# controle_motor_chave.net
KiCad netlist of a schematic drawn in Altium Designer
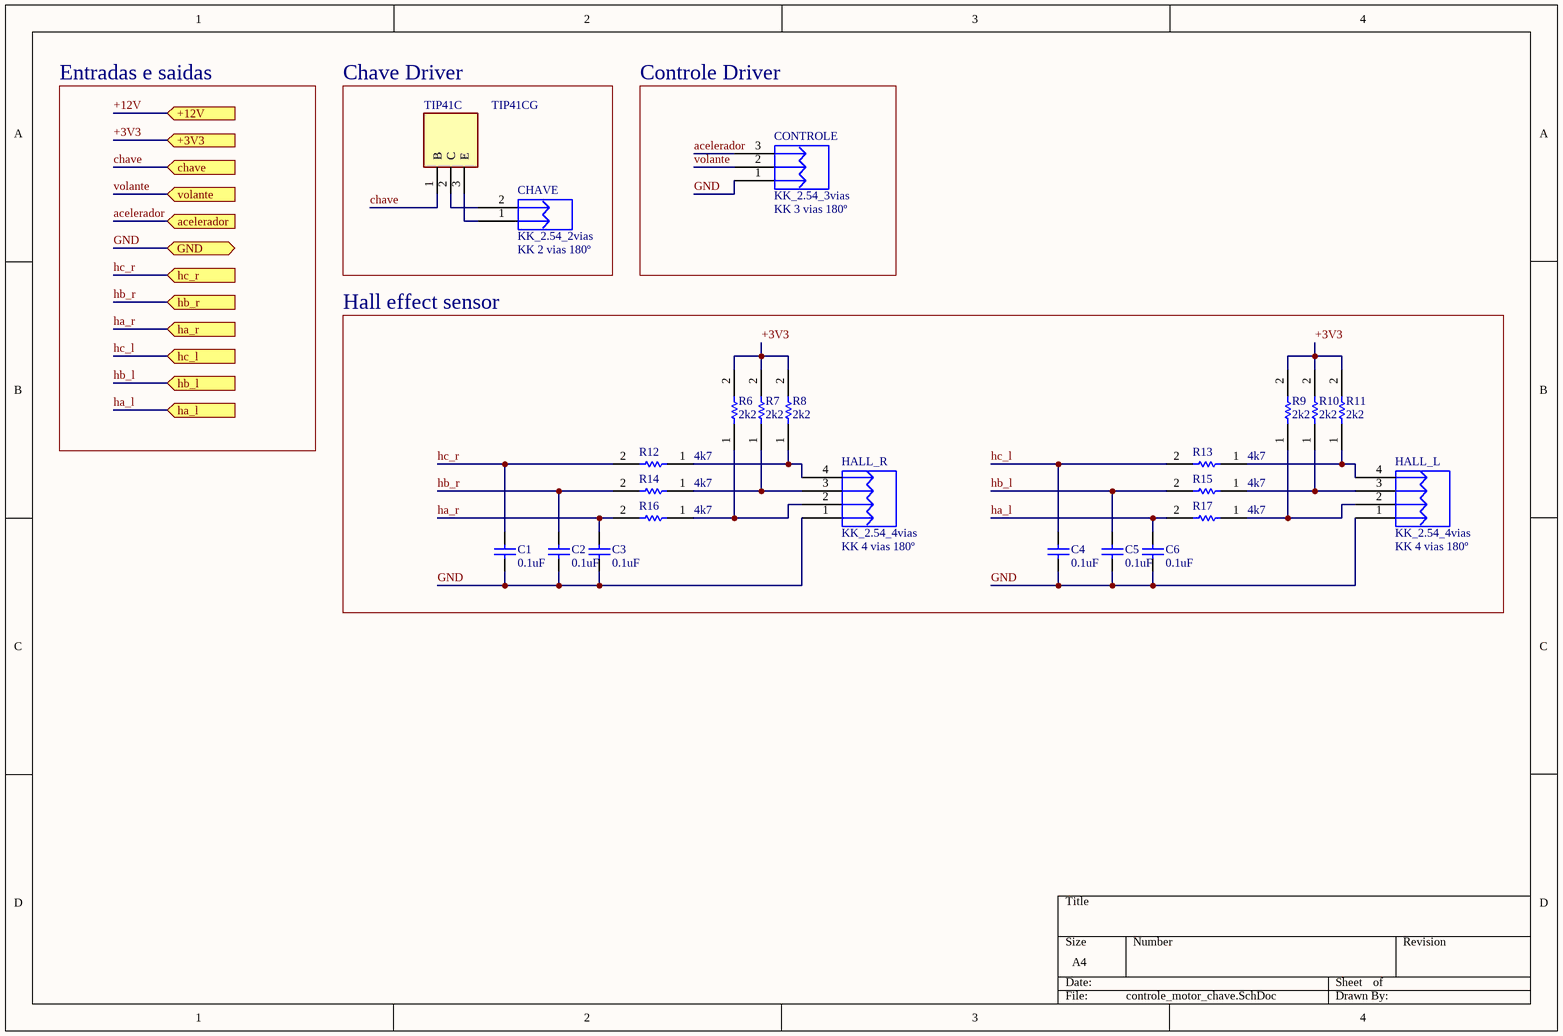
[diagram p0: controle_motor_chave.SchDoc]

(export (version "E")
  (design (tool "Eeschema 10.0.6"))
  (components
    (comp (ref "C1")
      (value "0.1uF")
      (footprint "CAP CER DISK 0.1uF")
      (description "CAP CER DISK 0.1uF")
      (fields (field (name "MANUFACTURER PART NUMBER") "IMP14925"))
      (libsource (lib "RoboHospitalar") (part "CAP CER DISK 0.1uF"))
    )
    (comp (ref "C2")
      (value "0.1uF")
      (footprint "CAP CER DISK 0.1uF")
      (description "CAP CER DISK 0.1uF")
      (fields (field (name "MANUFACTURER PART NUMBER") "IMP14925"))
      (libsource (lib "RoboHospitalar") (part "CAP CER DISK 0.1uF"))
    )
    (comp (ref "C3")
      (value "0.1uF")
      (footprint "CAP CER DISK 0.1uF")
      (description "CAP CER DISK 0.1uF")
      (fields (field (name "MANUFACTURER PART NUMBER") "IMP14925"))
      (libsource (lib "RoboHospitalar") (part "CAP CER DISK 0.1uF"))
    )
    (comp (ref "C4")
      (value "0.1uF")
      (footprint "CAP CER DISK 0.1uF")
      (description "CAP CER DISK 0.1uF")
      (fields (field (name "MANUFACTURER PART NUMBER") "IMP14925"))
      (libsource (lib "RoboHospitalar") (part "CAP CER DISK 0.1uF"))
    )
    (comp (ref "C5")
      (value "0.1uF")
      (footprint "CAP CER DISK 0.1uF")
      (description "CAP CER DISK 0.1uF")
      (fields (field (name "MANUFACTURER PART NUMBER") "IMP14925"))
      (libsource (lib "RoboHospitalar") (part "CAP CER DISK 0.1uF"))
    )
    (comp (ref "C6")
      (value "0.1uF")
      (footprint "CAP CER DISK 0.1uF")
      (description "CAP CER DISK 0.1uF")
      (fields (field (name "MANUFACTURER PART NUMBER") "IMP14925"))
      (libsource (lib "RoboHospitalar") (part "CAP CER DISK 0.1uF"))
    )
    (comp (ref "CHAVE")
      (value "KK_2.54_2vias")
      (footprint "KK_2VIAS_180º")
      (description "Conector KK 2.54mm 2 vias")
      (fields (field (name "VALOR") "KK 2 vias 180º"))
      (libsource (lib "Conectores_Sch") (part "KK_2.54_2vias"))
    )
    (comp (ref "CONTROLE")
      (value "KK_2.54_3vias")
      (footprint "KK_3vias_180º")
      (description "Conector KK 2.54mm 3 vias")
      (fields (field (name "VALOR") "KK 3 vias 180º"))
      (libsource (lib "Conectores_Sch") (part "KK_2.54_3vias"))
    )
    (comp (ref "HALL_L")
      (value "KK_2.54_4vias")
      (footprint "KK_4vias_180°")
      (description "Conector KK 2.54mm 4 vias")
      (fields (field (name "VALOR") "KK 4 vias 180º"))
      (libsource (lib "Conectores_Sch") (part "KK_2.54_4vias"))
    )
    (comp (ref "HALL_R")
      (value "KK_2.54_4vias")
      (footprint "KK_4vias_180°")
      (description "Conector KK 2.54mm 4 vias")
      (fields (field (name "VALOR") "KK 4 vias 180º"))
      (libsource (lib "Conectores_Sch") (part "KK_2.54_4vias"))
    )
    (comp (ref "R6")
      (value "2k2")
      (footprint "RESC3216X60N")
      (description "Resistor")
      (fields
        (field (name "MANUFACTURER_PART_NUMBER") "CRCW12064K70FKEA")
        (field (name "MOUSER PART NUMBER") "71-CRCW1206-4.7K-E3")
      )
      (libsource (lib "Sinaliza玢o_Official") (part "Resistor 1206"))
    )
    (comp (ref "R7")
      (value "2k2")
      (footprint "RESC3216X60N")
      (description "Resistor")
      (fields
        (field (name "MANUFACTURER_PART_NUMBER") "CRCW12064K70FKEA")
        (field (name "MOUSER PART NUMBER") "71-CRCW1206-4.7K-E3")
      )
      (libsource (lib "Sinaliza玢o_Official") (part "Resistor 1206"))
    )
    (comp (ref "R8")
      (value "2k2")
      (footprint "RESC3216X60N")
      (description "Resistor")
      (fields
        (field (name "MANUFACTURER_PART_NUMBER") "CRCW12064K70FKEA")
        (field (name "MOUSER PART NUMBER") "71-CRCW1206-4.7K-E3")
      )
      (libsource (lib "Sinaliza玢o_Official") (part "Resistor 1206"))
    )
    (comp (ref "R9")
      (value "2k2")
      (footprint "RESC3216X60N")
      (description "Resistor")
      (fields
        (field (name "MANUFACTURER_PART_NUMBER") "CRCW12064K70FKEA")
        (field (name "MOUSER PART NUMBER") "71-CRCW1206-4.7K-E3")
      )
      (libsource (lib "Sinaliza玢o_Official") (part "Resistor 1206"))
    )
    (comp (ref "R10")
      (value "2k2")
      (footprint "RESC3216X60N")
      (description "Resistor")
      (fields
        (field (name "MANUFACTURER_PART_NUMBER") "CRCW12064K70FKEA")
        (field (name "MOUSER PART NUMBER") "71-CRCW1206-4.7K-E3")
      )
      (libsource (lib "Sinaliza玢o_Official") (part "Resistor 1206"))
    )
    (comp (ref "R11")
      (value "2k2")
      (footprint "RESC3216X60N")
      (description "Resistor")
      (fields
        (field (name "MANUFACTURER_PART_NUMBER") "CRCW12064K70FKEA")
        (field (name "MOUSER PART NUMBER") "71-CRCW1206-4.7K-E3")
      )
      (libsource (lib "Sinaliza玢o_Official") (part "Resistor 1206"))
    )
    (comp (ref "R12")
      (value "4k7")
      (footprint "RESC3216X60N")
      (description "RES 1206 5%")
      (fields
        (field (name "MANUFACTURER_PART_NUMBER") "CRCW12064K70FKEA")
        (field (name "MOUSER PART NUMBER") "71-CRCW1206-4.7K-E3")
      )
      (libsource (lib "RoboHospitalar") (part "RES 1206"))
    )
    (comp (ref "R13")
      (value "4k7")
      (footprint "RESC3216X60N")
      (description "RES 1206 5%")
      (fields
        (field (name "MANUFACTURER_PART_NUMBER") "CRCW12064K70FKEA")
        (field (name "MOUSER PART NUMBER") "71-CRCW1206-4.7K-E3")
      )
      (libsource (lib "RoboHospitalar") (part "RES 1206"))
    )
    (comp (ref "R14")
      (value "4k7")
      (footprint "RESC3216X60N")
      (description "RES 1206 5%")
      (fields
        (field (name "MANUFACTURER_PART_NUMBER") "CRCW12064K70FKEA")
        (field (name "MOUSER PART NUMBER") "71-CRCW1206-4.7K-E3")
      )
      (libsource (lib "RoboHospitalar") (part "RES 1206"))
    )
    (comp (ref "R15")
      (value "4k7")
      (footprint "RESC3216X60N")
      (description "RES 1206 5%")
      (fields
        (field (name "MANUFACTURER_PART_NUMBER") "CRCW12064K70FKEA")
        (field (name "MOUSER PART NUMBER") "71-CRCW1206-4.7K-E3")
      )
      (libsource (lib "RoboHospitalar") (part "RES 1206"))
    )
    (comp (ref "R16")
      (value "4k7")
      (footprint "RESC3216X60N")
      (description "RES 1206 5%")
      (fields
        (field (name "MANUFACTURER_PART_NUMBER") "CRCW12064K70FKEA")
        (field (name "MOUSER PART NUMBER") "71-CRCW1206-4.7K-E3")
      )
      (libsource (lib "RoboHospitalar") (part "RES 1206"))
    )
    (comp (ref "R17")
      (value "4k7")
      (footprint "RESC3216X60N")
      (description "RES 1206 5%")
      (fields
        (field (name "MANUFACTURER_PART_NUMBER") "CRCW12064K70FKEA")
        (field (name "MOUSER PART NUMBER") "71-CRCW1206-4.7K-E3")
      )
      (libsource (lib "RoboHospitalar") (part "RES 1206"))
    )
    (comp (ref "TIP41C")
      (value "TIP41CG")
      (footprint "TO254P483X1010X2035-3P")
      (description "Transistor")
      (fields (field (name "MOUSER PART NUMBER") "863-TIP41CG"))
      (libsource (lib "RoboHospitalar") (part "TIP41CG"))
    )
  )
  (nets
    (net (code "1") (name "/+3V3") (class "Default")
      (node (ref "R10") (pin "2") (pinfunction "2_2") (pintype "passive"))
      (node (ref "R11") (pin "2") (pinfunction "2_2") (pintype "passive"))
      (node (ref "R6") (pin "2") (pinfunction "2_2") (pintype "passive"))
      (node (ref "R7") (pin "2") (pinfunction "2_2") (pintype "passive"))
      (node (ref "R8") (pin "2") (pinfunction "2_2") (pintype "passive"))
      (node (ref "R9") (pin "2") (pinfunction "2_2") (pintype "passive"))
    )
    (net (code "3") (name "/GND") (class "Default")
      (node (ref "C1") (pin "1") (pinfunction "1_1") (pintype "passive"))
      (node (ref "C2") (pin "1") (pinfunction "1_1") (pintype "passive"))
      (node (ref "C3") (pin "1") (pinfunction "1_1") (pintype "passive"))
      (node (ref "C4") (pin "1") (pinfunction "1_1") (pintype "passive"))
      (node (ref "C5") (pin "1") (pinfunction "1_1") (pintype "passive"))
      (node (ref "C6") (pin "1") (pinfunction "1_1") (pintype "passive"))
      (node (ref "CONTROLE") (pin "1") (pintype "passive"))
      (node (ref "HALL_L") (pin "1") (pintype "passive"))
      (node (ref "HALL_R") (pin "1") (pintype "passive"))
    )
    (net (code "4") (name "/acelerador") (class "Default")
      (node (ref "CONTROLE") (pin "3") (pintype "passive"))
    )
    (net (code "5") (name "/chave") (class "Default")
      (node (ref "TIP41C") (pin "1") (pinfunction "B_1") (pintype "passive"))
    )
    (net (code "6") (name "/ha_l") (class "Default")
      (node (ref "C6") (pin "2") (pinfunction "2_2") (pintype "passive"))
      (node (ref "R17") (pin "2") (pinfunction "2_2") (pintype "passive"))
    )
    (net (code "7") (name "/ha_r") (class "Default")
      (node (ref "C3") (pin "2") (pinfunction "2_2") (pintype "passive"))
      (node (ref "R16") (pin "2") (pinfunction "2_2") (pintype "passive"))
    )
    (net (code "8") (name "/hb_l") (class "Default")
      (node (ref "C5") (pin "2") (pinfunction "2_2") (pintype "passive"))
      (node (ref "R15") (pin "2") (pinfunction "2_2") (pintype "passive"))
    )
    (net (code "9") (name "/hb_r") (class "Default")
      (node (ref "C2") (pin "2") (pinfunction "2_2") (pintype "passive"))
      (node (ref "R14") (pin "2") (pinfunction "2_2") (pintype "passive"))
    )
    (net (code "10") (name "/hc_l") (class "Default")
      (node (ref "C4") (pin "2") (pinfunction "2_2") (pintype "passive"))
      (node (ref "R13") (pin "2") (pinfunction "2_2") (pintype "passive"))
    )
    (net (code "11") (name "/hc_r") (class "Default")
      (node (ref "C1") (pin "2") (pinfunction "2_2") (pintype "passive"))
      (node (ref "R12") (pin "2") (pinfunction "2_2") (pintype "passive"))
    )
    (net (code "12") (name "/volante") (class "Default")
      (node (ref "CONTROLE") (pin "2") (pintype "passive"))
    )
    (net (code "13") (name "Net-(HALL_L-Pad2)") (class "Default")
      (node (ref "HALL_L") (pin "2") (pintype "passive"))
      (node (ref "R17") (pin "1") (pinfunction "1_1") (pintype "passive"))
      (node (ref "R9") (pin "1") (pinfunction "1_1") (pintype "passive"))
    )
    (net (code "14") (name "Net-(HALL_L-Pad3)") (class "Default")
      (node (ref "HALL_L") (pin "3") (pintype "passive"))
      (node (ref "R10") (pin "1") (pinfunction "1_1") (pintype "passive"))
      (node (ref "R15") (pin "1") (pinfunction "1_1") (pintype "passive"))
    )
    (net (code "15") (name "Net-(HALL_L-Pad4)") (class "Default")
      (node (ref "HALL_L") (pin "4") (pintype "passive"))
      (node (ref "R11") (pin "1") (pinfunction "1_1") (pintype "passive"))
      (node (ref "R13") (pin "1") (pinfunction "1_1") (pintype "passive"))
    )
    (net (code "16") (name "Net-(HALL_R-Pad2)") (class "Default")
      (node (ref "HALL_R") (pin "2") (pintype "passive"))
      (node (ref "R16") (pin "1") (pinfunction "1_1") (pintype "passive"))
      (node (ref "R6") (pin "1") (pinfunction "1_1") (pintype "passive"))
    )
    (net (code "17") (name "Net-(HALL_R-Pad3)") (class "Default")
      (node (ref "HALL_R") (pin "3") (pintype "passive"))
      (node (ref "R14") (pin "1") (pinfunction "1_1") (pintype "passive"))
      (node (ref "R7") (pin "1") (pinfunction "1_1") (pintype "passive"))
    )
    (net (code "18") (name "Net-(HALL_R-Pad4)") (class "Default")
      (node (ref "HALL_R") (pin "4") (pintype "passive"))
      (node (ref "R12") (pin "1") (pinfunction "1_1") (pintype "passive"))
      (node (ref "R8") (pin "1") (pinfunction "1_1") (pintype "passive"))
    )
    (net (code "19") (name "Net-(TIP41C-C)") (class "Default")
      (node (ref "CHAVE") (pin "2") (pintype "passive"))
      (node (ref "TIP41C") (pin "2") (pinfunction "C_2") (pintype "passive"))
    )
    (net (code "20") (name "Net-(TIP41C-E)") (class "Default")
      (node (ref "CHAVE") (pin "1") (pintype "passive"))
      (node (ref "TIP41C") (pin "3") (pinfunction "E_3") (pintype "passive"))
    )
  )
)
